# Sheet1.net
KiCad netlist of a schematic drawn in Altium Designer
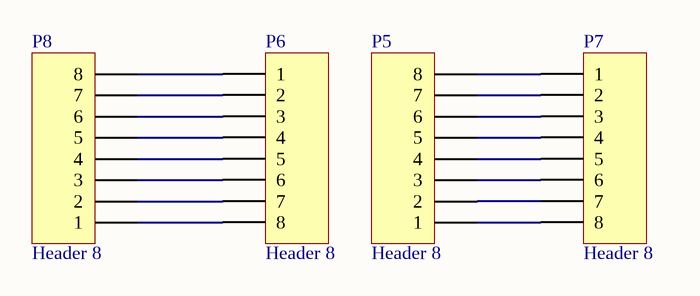
[diagram p0: Sheet1.SchDoc]

(export (version "E")
  (design (tool "Eeschema 10.0.6"))
  (components
    (comp (ref "P5")
      (value "Header 8")
      (footprint "HDR8")
      (description "Header, 8-Pin")
      (fields (field (name "PUBLISHER") "Altium Limited"))
      (libsource (lib "") (part "Header 8_1"))
    )
    (comp (ref "P6")
      (value "Header 8")
      (footprint "HDR8")
      (description "Header, 8-Pin")
      (fields (field (name "PUBLISHER") "Altium Limited"))
      (libsource (lib "Miscellaneous Connectors") (part "Header 8"))
    )
    (comp (ref "P7")
      (value "Header 8")
      (footprint "HDR8")
      (description "Header, 8-Pin")
      (fields (field (name "PUBLISHER") "Altium Limited"))
      (libsource (lib "Miscellaneous Connectors") (part "Header 8"))
    )
    (comp (ref "P8")
      (value "Header 8")
      (footprint "HDR8")
      (description "Header, 8-Pin")
      (fields (field (name "PUBLISHER") "Altium Limited"))
      (libsource (lib "") (part "Header 8_1"))
    )
  )
  (nets
    (net (code "1") (name "Net-(P5-Pad1)") (class "Default")
      (node (ref "P5") (pin "1") (pinfunction "1_1") (pintype "passive"))
      (node (ref "P7") (pin "8") (pinfunction "8_8") (pintype "passive"))
    )
    (net (code "2") (name "Net-(P5-Pad2)") (class "Default")
      (node (ref "P5") (pin "2") (pinfunction "2_2") (pintype "passive"))
      (node (ref "P7") (pin "7") (pinfunction "7_7") (pintype "passive"))
    )
    (net (code "3") (name "Net-(P5-Pad3)") (class "Default")
      (node (ref "P5") (pin "3") (pinfunction "3_3") (pintype "passive"))
      (node (ref "P7") (pin "6") (pinfunction "6_6") (pintype "passive"))
    )
    (net (code "4") (name "Net-(P5-Pad4)") (class "Default")
      (node (ref "P5") (pin "4") (pinfunction "4_4") (pintype "passive"))
      (node (ref "P7") (pin "5") (pinfunction "5_5") (pintype "passive"))
    )
    (net (code "5") (name "Net-(P5-Pad5)") (class "Default")
      (node (ref "P5") (pin "5") (pinfunction "5_5") (pintype "passive"))
      (node (ref "P7") (pin "4") (pinfunction "4_4") (pintype "passive"))
    )
    (net (code "6") (name "Net-(P5-Pad6)") (class "Default")
      (node (ref "P5") (pin "6") (pinfunction "6_6") (pintype "passive"))
      (node (ref "P7") (pin "3") (pinfunction "3_3") (pintype "passive"))
    )
    (net (code "7") (name "Net-(P5-Pad7)") (class "Default")
      (node (ref "P5") (pin "7") (pinfunction "7_7") (pintype "passive"))
      (node (ref "P7") (pin "2") (pinfunction "2_2") (pintype "passive"))
    )
    (net (code "8") (name "Net-(P5-Pad8)") (class "Default")
      (node (ref "P5") (pin "8") (pinfunction "8_8") (pintype "passive"))
      (node (ref "P7") (pin "1") (pinfunction "1_1") (pintype "passive"))
    )
    (net (code "9") (name "Net-(P6-Pad1)") (class "Default")
      (node (ref "P6") (pin "1") (pinfunction "1_1") (pintype "passive"))
      (node (ref "P8") (pin "8") (pinfunction "8_8") (pintype "passive"))
    )
    (net (code "10") (name "Net-(P6-Pad2)") (class "Default")
      (node (ref "P6") (pin "2") (pinfunction "2_2") (pintype "passive"))
      (node (ref "P8") (pin "7") (pinfunction "7_7") (pintype "passive"))
    )
    (net (code "11") (name "Net-(P6-Pad3)") (class "Default")
      (node (ref "P6") (pin "3") (pinfunction "3_3") (pintype "passive"))
      (node (ref "P8") (pin "6") (pinfunction "6_6") (pintype "passive"))
    )
    (net (code "12") (name "Net-(P6-Pad4)") (class "Default")
      (node (ref "P6") (pin "4") (pinfunction "4_4") (pintype "passive"))
      (node (ref "P8") (pin "5") (pinfunction "5_5") (pintype "passive"))
    )
    (net (code "13") (name "Net-(P6-Pad5)") (class "Default")
      (node (ref "P6") (pin "5") (pinfunction "5_5") (pintype "passive"))
      (node (ref "P8") (pin "4") (pinfunction "4_4") (pintype "passive"))
    )
    (net (code "14") (name "Net-(P6-Pad6)") (class "Default")
      (node (ref "P6") (pin "6") (pinfunction "6_6") (pintype "passive"))
      (node (ref "P8") (pin "3") (pinfunction "3_3") (pintype "passive"))
    )
    (net (code "15") (name "Net-(P6-Pad7)") (class "Default")
      (node (ref "P6") (pin "7") (pinfunction "7_7") (pintype "passive"))
      (node (ref "P8") (pin "2") (pinfunction "2_2") (pintype "passive"))
    )
    (net (code "16") (name "Net-(P6-Pad8)") (class "Default")
      (node (ref "P6") (pin "8") (pinfunction "8_8") (pintype "passive"))
      (node (ref "P8") (pin "1") (pinfunction "1_1") (pintype "passive"))
    )
  )
)
